# SCH_PC-Engine-Controller-Breakout_2024-1.net
KiCad netlist of a schematic drawn in EasyEDA
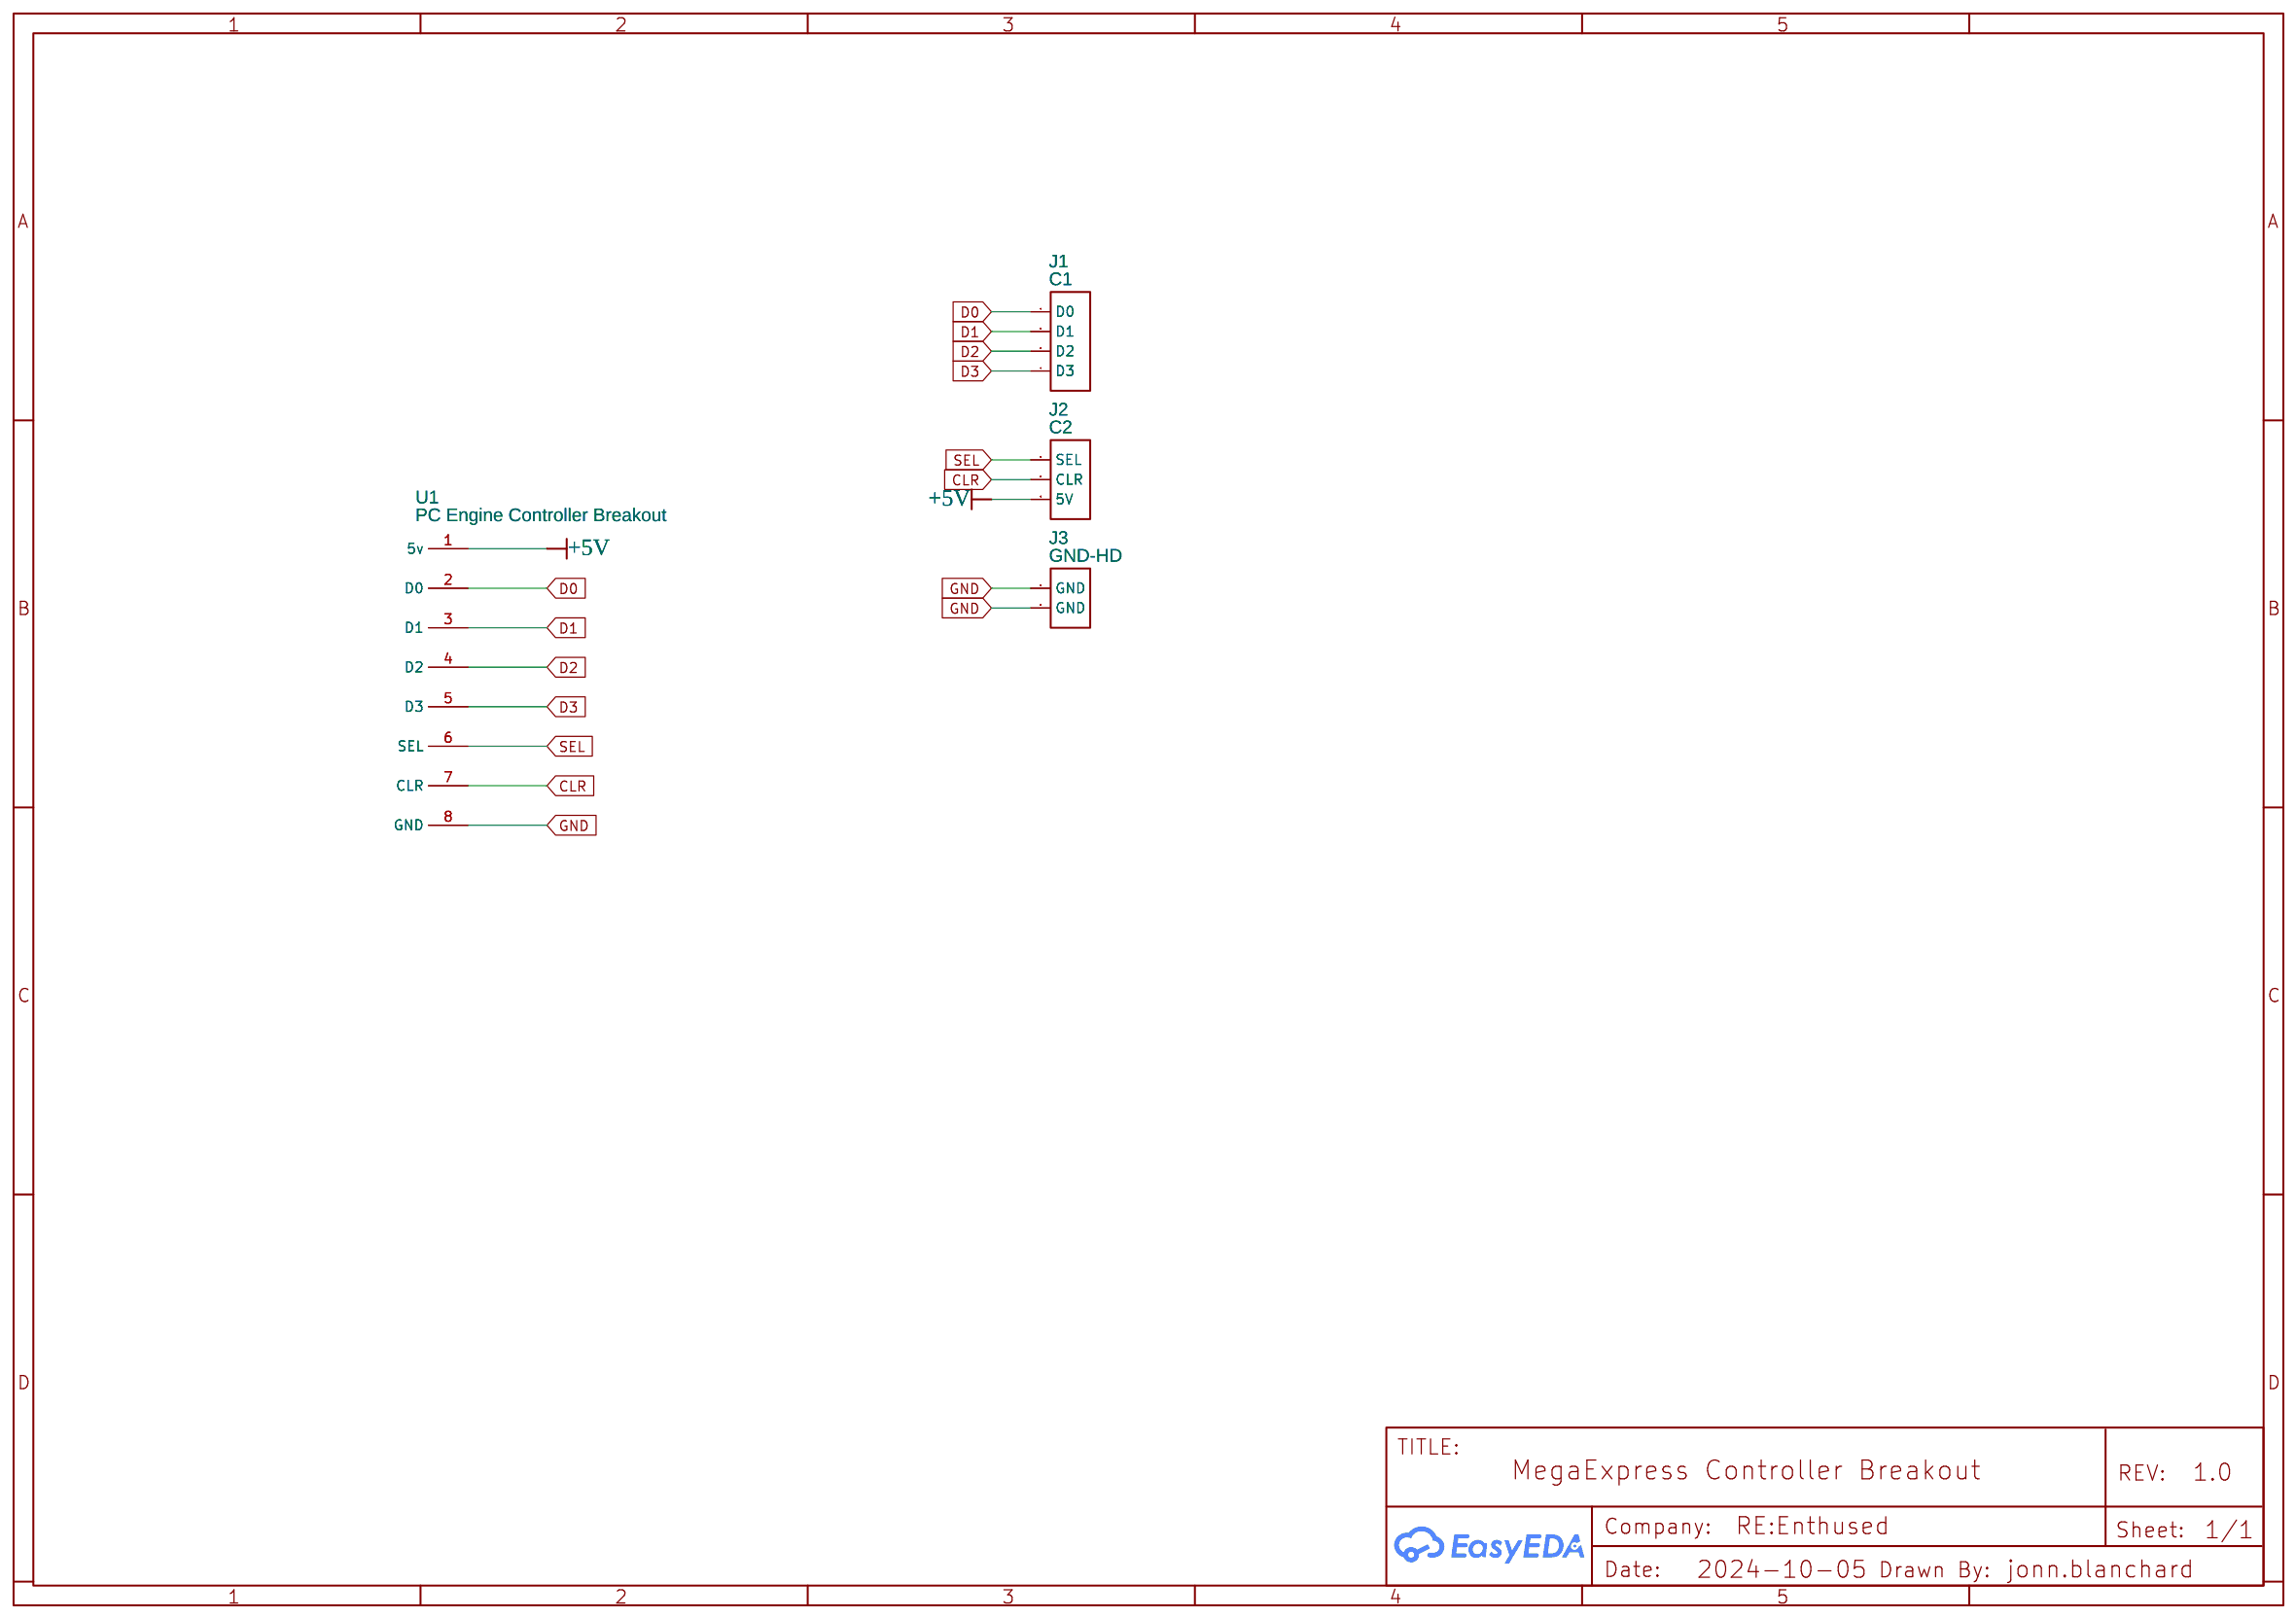
[diagram p0: schematic sheet]

(export (version "E")
  (design (tool "Eeschema 10.0.6"))
  (components
    (comp (ref "J1") (value "C1") (libsource (lib "") (part "HDR-M-2.54_1x4")))
    (comp (ref "J2") (value "C2") (libsource (lib "") (part "HDR-M-2.54_1x3")))
    (comp (ref "J3") (value "GND-HD") (libsource (lib "") (part "HDR-M-2.54_1x2")))
    (comp (ref "U1")
      (value "PC Engine Controller Breakout")
      (libsource (lib "") (part "PC Engine Controller Breakout"))
    )
  )
  (nets
    (net (code "1") (name "+5V") (class "Default")
      (node (ref "J2") (pin "3") (pinfunction "5V_3") (pintype "input"))
      (node (ref "U1") (pin "1") (pinfunction "5v_1") (pintype "unspecified"))
    )
    (net (code "2") (name "CLR") (class "Default")
      (node (ref "J2") (pin "2") (pinfunction "CLR_2") (pintype "input"))
      (node (ref "U1") (pin "7") (pinfunction "CLR_7") (pintype "unspecified"))
    )
    (net (code "3") (name "D0") (class "Default")
      (node (ref "J1") (pin "1") (pinfunction "D0_1") (pintype "unspecified"))
      (node (ref "U1") (pin "2") (pinfunction "D0_2") (pintype "unspecified"))
    )
    (net (code "4") (name "D1") (class "Default")
      (node (ref "J1") (pin "2") (pinfunction "D1_2") (pintype "unspecified"))
      (node (ref "U1") (pin "3") (pinfunction "D1_3") (pintype "unspecified"))
    )
    (net (code "5") (name "D2") (class "Default")
      (node (ref "J1") (pin "3") (pinfunction "D2_3") (pintype "unspecified"))
      (node (ref "U1") (pin "4") (pinfunction "D2_4") (pintype "unspecified"))
    )
    (net (code "6") (name "D3") (class "Default")
      (node (ref "J1") (pin "4") (pinfunction "D3_4") (pintype "unspecified"))
      (node (ref "U1") (pin "5") (pinfunction "D3_5") (pintype "unspecified"))
    )
    (net (code "7") (name "GND") (class "Default")
      (node (ref "J3") (pin "1") (pinfunction "GND_1") (pintype "unspecified"))
      (node (ref "J3") (pin "2") (pinfunction "GND_2") (pintype "unspecified"))
      (node (ref "U1") (pin "8") (pinfunction "GND_8") (pintype "unspecified"))
    )
    (net (code "8") (name "SEL") (class "Default")
      (node (ref "J2") (pin "1") (pinfunction "SEL_1") (pintype "input"))
      (node (ref "U1") (pin "6") (pinfunction "SEL_6") (pintype "unspecified"))
    )
  )
)
